# LC_Board.net
KiCad netlist of a schematic drawn in EAGLE
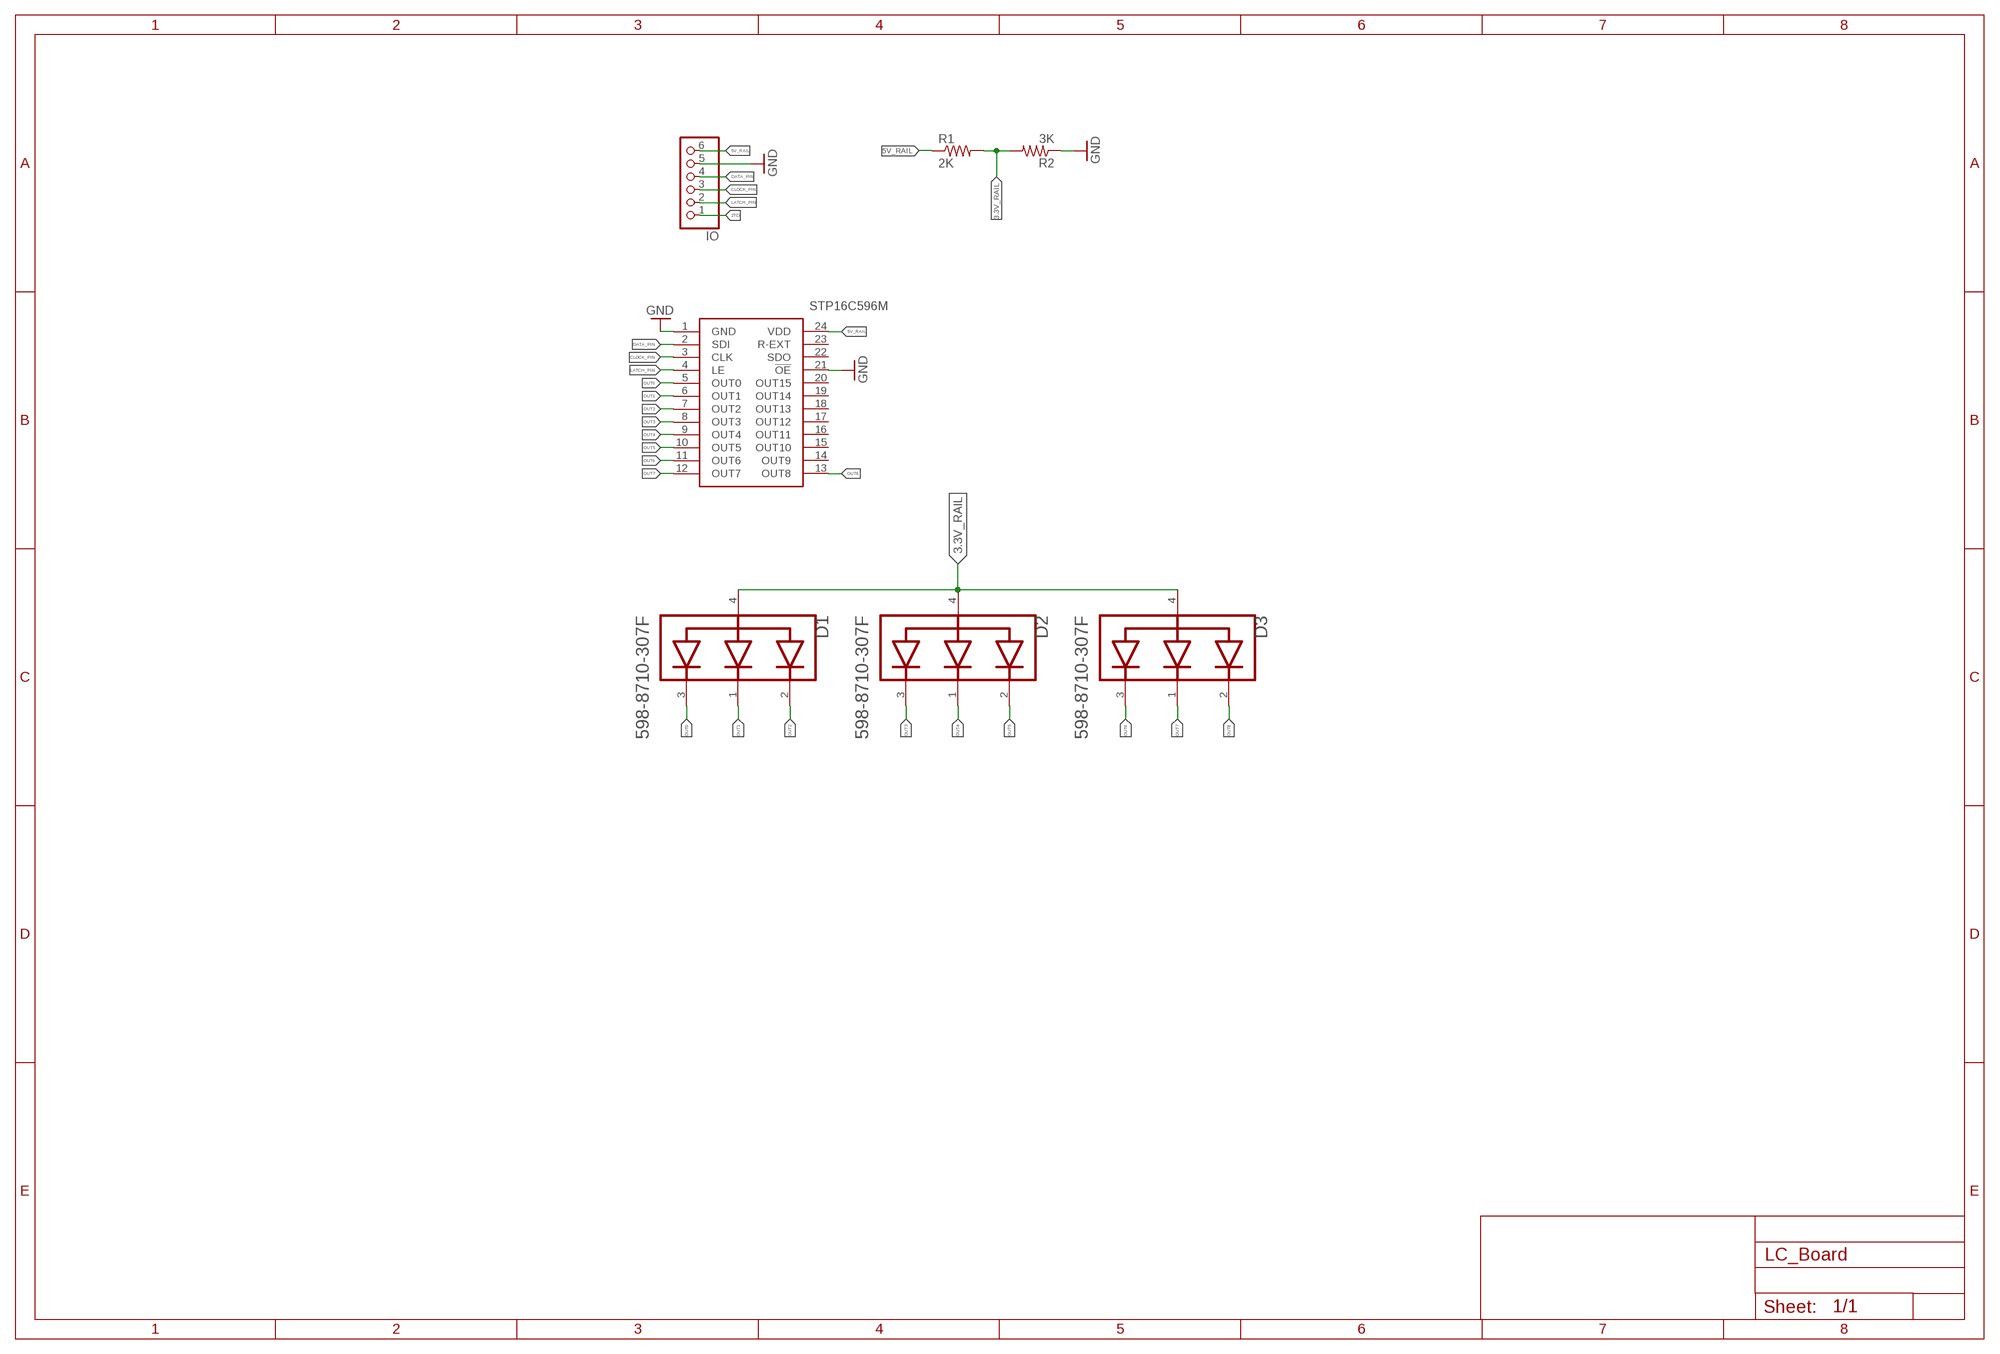
[diagram p0: schematic, sheet 1]

(export (version "E")
  (design (tool "Eeschema 10.0.6"))
  (components
    (comp (ref "D1")
      (value "DIALIGHT_598-8710-307FDIALIGHT_598-8710-307F_0_0")
      (footprint "eagle-import:DIALIGHT_598-8710-307F_0")
      (fields
        (field (name "DIGIKEY_PART_NUMBER") "350-2096-1-ND")
        (field (name "MF") "Dialight")
        (field (name "MOUSER_PART_NUMBER") "645-598-8710-307F")
        (field (name "SPICEPREFIX") "E")
      )
      (libsource (lib "eagle-import") (part "DIALIGHT_598-8710-307FDIALIGHT_598-8710-307F_0_0"))
    )
    (comp (ref "D2")
      (value "DIALIGHT_598-8710-307FDIALIGHT_598-8710-307F_0_0")
      (footprint "eagle-import:DIALIGHT_598-8710-307F_0")
      (fields
        (field (name "DIGIKEY_PART_NUMBER") "350-2096-1-ND")
        (field (name "MF") "Dialight")
        (field (name "MOUSER_PART_NUMBER") "645-598-8710-307F")
        (field (name "SPICEPREFIX") "E")
      )
      (libsource (lib "eagle-import") (part "DIALIGHT_598-8710-307FDIALIGHT_598-8710-307F_0_0"))
    )
    (comp (ref "D3")
      (value "DIALIGHT_598-8710-307FDIALIGHT_598-8710-307F_0_0")
      (footprint "eagle-import:DIALIGHT_598-8710-307F_0")
      (fields
        (field (name "DIGIKEY_PART_NUMBER") "350-2096-1-ND")
        (field (name "MF") "Dialight")
        (field (name "MOUSER_PART_NUMBER") "645-598-8710-307F")
        (field (name "SPICEPREFIX") "E")
      )
      (libsource (lib "eagle-import") (part "DIALIGHT_598-8710-307FDIALIGHT_598-8710-307F_0_0"))
    )
    (comp (ref "IC1")
      (value "STP16C596M")
      (footprint "eagle-import:SOP65P638X110-24N")
      (libsource (lib "eagle-import") (part "STP16C596M"))
    )
    (comp (ref "IO")
      (value "PINHD-1X6CLEAN")
      (footprint "eagle-import:1X06-CLEAN")
      (libsource (lib "eagle-import") (part "PINHD-1X6CLEAN"))
    )
    (comp (ref "R1")
      (value "2K")
      (footprint "eagle-import:0805-THM")
      (libsource (lib "eagle-import") (part "FLIPFLOP-RES"))
    )
    (comp (ref "R2")
      (value "3K")
      (footprint "eagle-import:0805-THM")
      (libsource (lib "eagle-import") (part "FLIPFLOP-RES"))
    )
  )
  (nets
    (net (code "1") (name "2TD") (class "Default")
      (node (ref "IO") (pin "1") (pinfunction "1_1") (pintype "passive"))
    )
    (net (code "2") (name "3.3V_RAIL") (class "Default")
      (node (ref "D1") (pin "4") (pinfunction "COMMON_ANODE_4") (pintype "bidirectional"))
      (node (ref "D2") (pin "4") (pinfunction "COMMON_ANODE_4") (pintype "bidirectional"))
      (node (ref "D3") (pin "4") (pinfunction "COMMON_ANODE_4") (pintype "bidirectional"))
      (node (ref "R1") (pin "2") (pinfunction "2_2") (pintype "passive"))
      (node (ref "R2") (pin "2") (pinfunction "2_2") (pintype "passive"))
    )
    (net (code "3") (name "5V_RAIL") (class "Default")
      (node (ref "IC1") (pin "24") (pinfunction "VDD_24") (pintype "bidirectional"))
      (node (ref "IO") (pin "6") (pinfunction "6_6") (pintype "passive"))
      (node (ref "R1") (pin "1") (pinfunction "1_1") (pintype "passive"))
    )
    (net (code "4") (name "CLOCK_PIN") (class "Default")
      (node (ref "IC1") (pin "3") (pinfunction "CLK_3") (pintype "input"))
      (node (ref "IO") (pin "3") (pinfunction "3_3") (pintype "passive"))
    )
    (net (code "5") (name "DATA_PIN") (class "Default")
      (node (ref "IC1") (pin "2") (pinfunction "SDI_2") (pintype "input"))
      (node (ref "IO") (pin "4") (pinfunction "4_4") (pintype "passive"))
    )
    (net (code "6") (name "GND") (class "Default")
      (node (ref "IC1") (pin "1") (pinfunction "GND_1") (pintype "power_in"))
      (node (ref "IC1") (pin "21") (pinfunction "~{OE}_21") (pintype "input"))
      (node (ref "IO") (pin "5") (pinfunction "5_5") (pintype "passive"))
      (node (ref "R2") (pin "1") (pinfunction "1_1") (pintype "passive"))
    )
    (net (code "7") (name "LATCH_PIN") (class "Default")
      (node (ref "IC1") (pin "4") (pinfunction "LE_4") (pintype "input"))
      (node (ref "IO") (pin "2") (pinfunction "2_2") (pintype "passive"))
    )
    (net (code "8") (name "OUT0") (class "Default")
      (node (ref "D1") (pin "3") (pinfunction "BLUE_CATHODE_3") (pintype "bidirectional"))
      (node (ref "IC1") (pin "5") (pinfunction "OUT0_5") (pintype "output"))
    )
    (net (code "9") (name "OUT1") (class "Default")
      (node (ref "D1") (pin "1") (pinfunction "GREEN_CATHODE_1") (pintype "bidirectional"))
      (node (ref "IC1") (pin "6") (pinfunction "OUT1_6") (pintype "output"))
    )
    (net (code "10") (name "OUT2") (class "Default")
      (node (ref "D1") (pin "2") (pinfunction "RED_CATHODE_2") (pintype "bidirectional"))
      (node (ref "IC1") (pin "7") (pinfunction "OUT2_7") (pintype "output"))
    )
    (net (code "11") (name "OUT3") (class "Default")
      (node (ref "D2") (pin "3") (pinfunction "BLUE_CATHODE_3") (pintype "bidirectional"))
      (node (ref "IC1") (pin "8") (pinfunction "OUT3_8") (pintype "output"))
    )
    (net (code "12") (name "OUT4") (class "Default")
      (node (ref "D2") (pin "1") (pinfunction "GREEN_CATHODE_1") (pintype "bidirectional"))
      (node (ref "IC1") (pin "9") (pinfunction "OUT4_9") (pintype "output"))
    )
    (net (code "13") (name "OUT5") (class "Default")
      (node (ref "D2") (pin "2") (pinfunction "RED_CATHODE_2") (pintype "bidirectional"))
      (node (ref "IC1") (pin "10") (pinfunction "OUT5_10") (pintype "output"))
    )
    (net (code "14") (name "OUT6") (class "Default")
      (node (ref "D3") (pin "3") (pinfunction "BLUE_CATHODE_3") (pintype "bidirectional"))
      (node (ref "IC1") (pin "11") (pinfunction "OUT6_11") (pintype "output"))
    )
    (net (code "15") (name "OUT7") (class "Default")
      (node (ref "D3") (pin "1") (pinfunction "GREEN_CATHODE_1") (pintype "bidirectional"))
      (node (ref "IC1") (pin "12") (pinfunction "OUT7_12") (pintype "output"))
    )
    (net (code "16") (name "OUT8") (class "Default")
      (node (ref "D3") (pin "2") (pinfunction "RED_CATHODE_2") (pintype "bidirectional"))
      (node (ref "IC1") (pin "13") (pinfunction "OUT8_13") (pintype "output"))
    )
    (net (code "17") (name "unconnected-(IC1-OUT9-Pad14)") (class "Default")
      (node (ref "IC1") (pin "14") (pinfunction "OUT9_14") (pintype "output"))
    )
    (net (code "18") (name "unconnected-(IC1-OUT10-Pad15)") (class "Default")
      (node (ref "IC1") (pin "15") (pinfunction "OUT10_15") (pintype "output"))
    )
    (net (code "19") (name "unconnected-(IC1-OUT11-Pad16)") (class "Default")
      (node (ref "IC1") (pin "16") (pinfunction "OUT11_16") (pintype "output"))
    )
    (net (code "20") (name "unconnected-(IC1-OUT12-Pad17)") (class "Default")
      (node (ref "IC1") (pin "17") (pinfunction "OUT12_17") (pintype "output"))
    )
    (net (code "21") (name "unconnected-(IC1-OUT13-Pad18)") (class "Default")
      (node (ref "IC1") (pin "18") (pinfunction "OUT13_18") (pintype "output"))
    )
    (net (code "22") (name "unconnected-(IC1-OUT14-Pad19)") (class "Default")
      (node (ref "IC1") (pin "19") (pinfunction "OUT14_19") (pintype "bidirectional"))
    )
    (net (code "23") (name "unconnected-(IC1-OUT15-Pad20)") (class "Default")
      (node (ref "IC1") (pin "20") (pinfunction "OUT15_20") (pintype "bidirectional"))
    )
    (net (code "24") (name "unconnected-(IC1-R-EXT-Pad23)") (class "Default")
      (node (ref "IC1") (pin "23") (pinfunction "R-EXT_23") (pintype "input"))
    )
    (net (code "25") (name "unconnected-(IC1-SDO-Pad22)") (class "Default")
      (node (ref "IC1") (pin "22") (pinfunction "SDO_22") (pintype "output"))
    )
  )
)
